# Microcontroller_schematic.net
KiCad netlist of a schematic drawn in Altium Designer
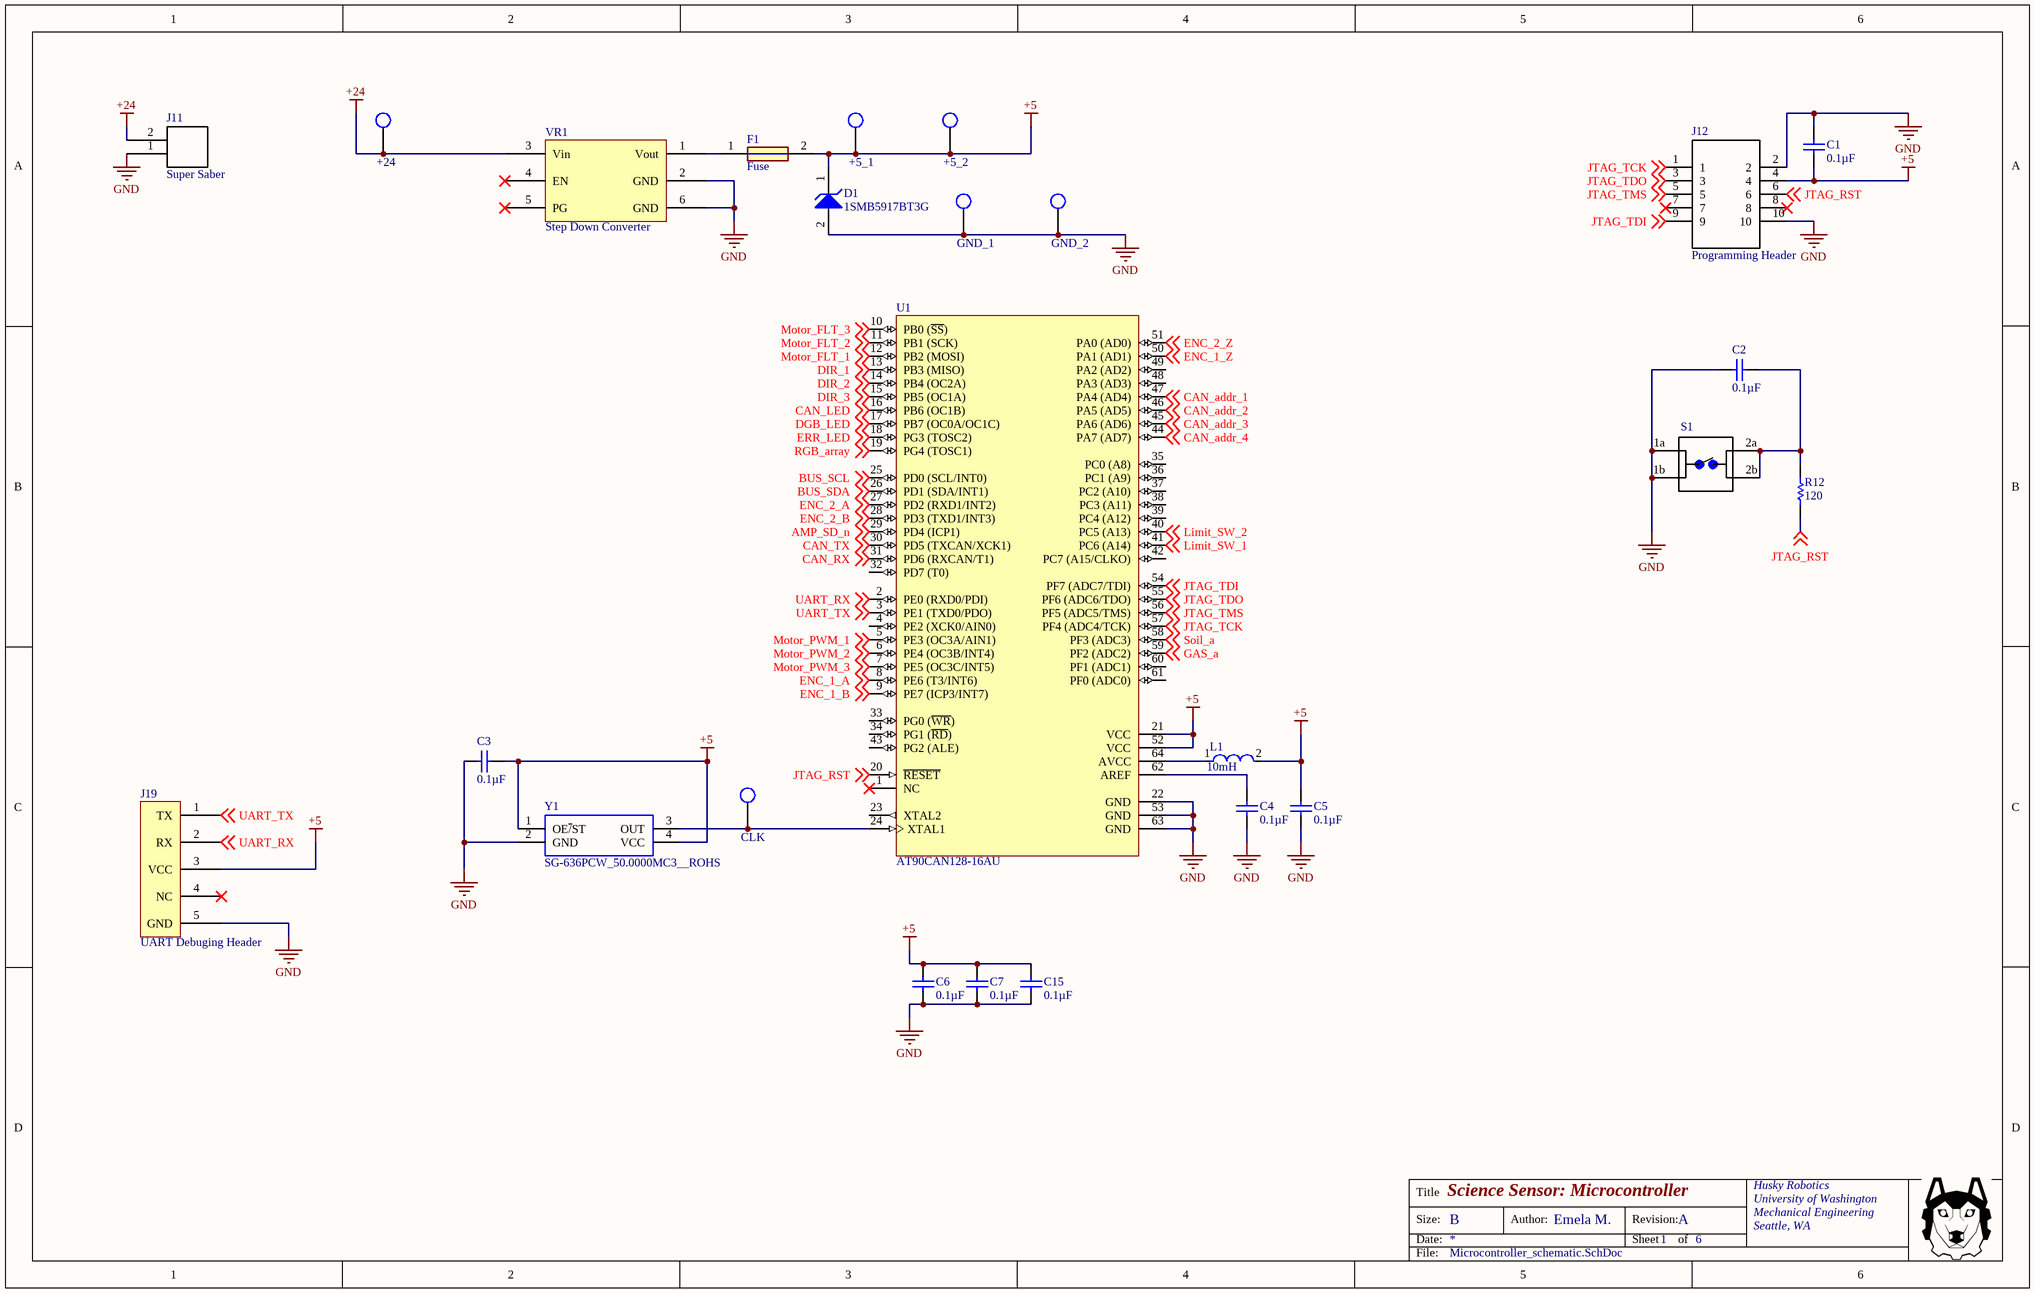
[diagram p0: Microcontroller_schematic.SchDoc]

(export (version "E")
  (design (tool "Eeschema 10.0.6"))
  (components
    (comp (ref "+5_1")
      (value "Test Point")
      (footprint "Test Point Through-hole")
      (libsource (lib "Husky Robotics Standard Library 2019-2020") (part "Test Point"))
    )
    (comp (ref "+5_2")
      (value "Test Point")
      (footprint "Test Point Through-hole")
      (libsource (lib "Husky Robotics Standard Library 2019-2020") (part "Test Point"))
    )
    (comp (ref "+24")
      (value "Test Point")
      (footprint "Test Point Through-hole")
      (libsource (lib "Husky Robotics Standard Library 2019-2020") (part "Test Point"))
    )
    (comp (ref "C1")
      (value "Capacitor 0805")
      (footprint "Cap 0805")
      (description "Standard Capacitor")
      (fields (field (name "MANUFACTURER") "AVX") (field (name "CAPACITANCE") "0.1µF"))
      (libsource (lib "Standard Cap") (part "Capacitor 0805"))
    )
    (comp (ref "C2")
      (value "Capacitor 0805")
      (footprint "Cap 0805")
      (description "Standard Capacitor")
      (fields (field (name "MANUFACTURER") "AVX") (field (name "CAPACITANCE") "0.1µF"))
      (libsource (lib "Standard Cap") (part "Capacitor 0805"))
    )
    (comp (ref "C3")
      (value "Capacitor 0805")
      (footprint "Cap 0805")
      (description "Standard Capacitor")
      (fields (field (name "MANUFACTURER") "AVX") (field (name "CAPACITANCE") "0.1µF"))
      (libsource (lib "Standard Cap") (part "Capacitor 0805"))
    )
    (comp (ref "C4")
      (value "Capacitor 0805")
      (footprint "Cap 0805")
      (description "Standard Capacitor")
      (fields (field (name "MANUFACTURER") "AVX") (field (name "CAPACITANCE") "0.1µF"))
      (libsource (lib "Standard Cap") (part "Capacitor 0805"))
    )
    (comp (ref "C5")
      (value "Capacitor 0805")
      (footprint "Cap 0805")
      (description "Standard Capacitor")
      (fields (field (name "MANUFACTURER") "AVX") (field (name "CAPACITANCE") "0.1µF"))
      (libsource (lib "Standard Cap") (part "Capacitor 0805"))
    )
    (comp (ref "C6")
      (value "Capacitor 0805")
      (footprint "Cap 0805")
      (description "Standard Capacitor")
      (fields (field (name "MANUFACTURER") "AVX") (field (name "CAPACITANCE") "0.1µF"))
      (libsource (lib "Standard Cap") (part "Capacitor 0805"))
    )
    (comp (ref "C7")
      (value "Capacitor 0805")
      (footprint "Cap 0805")
      (description "Standard Capacitor")
      (fields (field (name "MANUFACTURER") "AVX") (field (name "CAPACITANCE") "0.1µF"))
      (libsource (lib "Standard Cap") (part "Capacitor 0805"))
    )
    (comp (ref "C15")
      (value "Capacitor 0805")
      (footprint "Cap 0805")
      (description "Standard Capacitor")
      (fields (field (name "MANUFACTURER") "AVX") (field (name "CAPACITANCE") "0.1µF"))
      (libsource (lib "Standard Cap") (part "Capacitor 0805"))
    )
    (comp (ref "CLK")
      (value "Test Point")
      (footprint "Test Point Through-hole")
      (libsource (lib "Husky Robotics Standard Library 2019-2020") (part "Test Point"))
    )
    (comp (ref "D1")
      (value "1SMB5917BT3G")
      (footprint "ONSC-SMB-2-403A-03_H_V")
      (description "3 W Zener Voltage Regulator, 2-Pin SMB, Pb-Free, Tape and Reel")
      (fields (field (name "MANUFACTURER") "On Semiconductor"))
      (libsource (lib "Husky Robotics Standard Library 2019-2020") (part "Zener Diode 5.1V"))
    )
    (comp (ref "F1")
      (value "Fuse")
      (footprint "Fuse_Through_Hole - duplicate")
      (libsource (lib "Husky Robotics Standard Library 2019-2020") (part "Fuse"))
    )
    (comp (ref "GND_1")
      (value "Test Point")
      (footprint "Test Point Through-hole")
      (libsource (lib "Husky Robotics Standard Library 2019-2020") (part "Test Point"))
    )
    (comp (ref "GND_2")
      (value "Test Point")
      (footprint "Test Point Through-hole")
      (libsource (lib "Husky Robotics Standard Library 2019-2020") (part "Test Point"))
    )
    (comp (ref "J11")
      (value "Super Saber")
      (footprint "SuperSaber R/A")
      (libsource (lib "Husky Robotics Standard Library 2019-2020") (part "Super Saber"))
    )
    (comp (ref "J12")
      (value "Programming Header")
      (footprint "programming3D")
      (libsource (lib "Husky Robotics Standard Library 2019-2020") (part "Programming Header"))
    )
    (comp (ref "J19")
      (value "UART Debuging Header")
      (footprint "UART Debugging Header")
      (libsource (lib "Husky Robotics Standard Library 2019-2020") (part "UART Debuging Header"))
    )
    (comp (ref "L1")
      (value "10mH")
      (footprint "FP-CV201210-R10K-MFG")
      (description "FIXED IND 100NH 250MA 300 MOHM")
      (fields
        (field (name "TOLERANCE") "10%")
        (field (name "OCTOPART") "https://octopart.com/cv201210-r10k-bourns-2076708")
      )
      (libsource (lib "Altium Content Vault") (part "725321dda6339637d4d059423bc1c3c"))
    )
    (comp (ref "R12")
      (value "120")
      (footprint "RESC0805(2012)_N")
      (description "Generic 0805 Resistor")
      (fields (field (name "TOLERANCE") "5 %") (field (name "POWER") "0.125 W"))
      (libsource (lib "Husky Robotics Standard Library 2019-2020") (part "Resistor 0805"))
    )
    (comp (ref "S1")
      (value "1825910-7")
      (footprint "Switch 6mm 24V (NO)")
      (description "FSM4JAH=6MM TACT SWITCH, HIGH TEMP")
      (fields (field (name "MF") "TE Connectivity") (field (name "DIGI-KEY_PART_NUMBER") "450-1804-ND"))
      (libsource (lib "Husky Robotics Standard Library 2019-2020") (part "Switch 6mm 24V (NO)"))
    )
    (comp (ref "U1")
      (value "AT90CAN128-16AU")
      (footprint "64A_M")
      (libsource (lib "Altium Content Vault") (part "MC-8B-AT90CAN32-SQ64"))
    )
    (comp (ref "VR1")
      (value "Step Down Converter")
      (footprint "24V-5V Converter")
      (libsource (lib "Husky Robotics Standard Library 2019-2020") (part "24V-5V Pololu 2858"))
    )
    (comp (ref "Y1")
      (value "SG-636PCW_50.0000MC3__ROHS")
      (footprint "SG-636_3D")
      (description "Standard Clock Oscillators")
      (fields (field (name "MANUFACTURER_PART_NUMBER") "SG-636PCW 50.0000MC3: ROHS"))
      (libsource (lib "Husky Robotics Standard Library 2019-2020") (part "Oscilator"))
    )
  )
  (nets
    (net (code "1") (name "+5") (class "Default")
      (node (ref "+5_1") (pin "1") (pinfunction "1_1") (pintype "passive"))
      (node (ref "+5_2") (pin "1") (pinfunction "1_1") (pintype "passive"))
      (node (ref "C1") (pin "1") (pinfunction "1_1") (pintype "passive"))
      (node (ref "C15") (pin "2") (pinfunction "2_2") (pintype "passive"))
      (node (ref "C3") (pin "2") (pinfunction "2_2") (pintype "passive"))
      (node (ref "C5") (pin "2") (pinfunction "2_2") (pintype "passive"))
      (node (ref "C6") (pin "2") (pinfunction "2_2") (pintype "passive"))
      (node (ref "C7") (pin "2") (pinfunction "2_2") (pintype "passive"))
      (node (ref "D1") (pin "1") (pinfunction "K_1") (pintype "passive"))
      (node (ref "F1") (pin "2") (pinfunction "2_2") (pintype "passive"))
      (node (ref "J12") (pin "4") (pinfunction "4_4") (pintype "passive"))
      (node (ref "J19") (pin "3") (pinfunction "VCC_3") (pintype "passive"))
      (node (ref "L1") (pin "2") (pinfunction "2_2") (pintype "passive"))
      (node (ref "U1") (pin "21") (pinfunction "VCC_21") (pintype "power_in"))
      (node (ref "U1") (pin "52") (pinfunction "VCC_52") (pintype "power_in"))
      (node (ref "Y1") (pin "1") (pinfunction "OE~{/}ST_1") (pintype "passive"))
      (node (ref "Y1") (pin "4") (pinfunction "VCC_4") (pintype "power_in"))
    )
    (net (code "2") (name "+24") (class "Default")
      (node (ref "+24") (pin "1") (pinfunction "1_1") (pintype "passive"))
      (node (ref "J11") (pin "2") (pintype "passive"))
      (node (ref "VR1") (pin "3") (pinfunction "Vin_3") (pintype "passive"))
    )
    (net (code "3") (name "AMP_SD_n") (class "Default")
      (node (ref "U1") (pin "29") (pinfunction "PD4_(ICP1)_29") (pintype "bidirectional"))
    )
    (net (code "4") (name "BUS_SCL") (class "Default")
      (node (ref "U1") (pin "25") (pinfunction "PD0_(SCL/INT0)_25") (pintype "bidirectional"))
    )
    (net (code "5") (name "BUS_SDA") (class "Default")
      (node (ref "U1") (pin "26") (pinfunction "PD1_(SDA/INT1)_26") (pintype "bidirectional"))
    )
    (net (code "6") (name "CAN_LED") (class "Default")
      (node (ref "U1") (pin "16") (pinfunction "PB6_(OC1B)_16") (pintype "bidirectional"))
    )
    (net (code "7") (name "CAN_RX") (class "Default")
      (node (ref "U1") (pin "31") (pinfunction "PD6_(RXCAN/T1)_31") (pintype "bidirectional"))
    )
    (net (code "8") (name "CAN_TX") (class "Default")
      (node (ref "U1") (pin "30") (pinfunction "PD5_(TXCAN/XCK1)_30") (pintype "bidirectional"))
    )
    (net (code "9") (name "CAN_addr_1") (class "Default")
      (node (ref "U1") (pin "47") (pinfunction "PA4_(AD4)_47") (pintype "bidirectional"))
    )
    (net (code "10") (name "CAN_addr_2") (class "Default")
      (node (ref "U1") (pin "46") (pinfunction "PA5_(AD5)_46") (pintype "bidirectional"))
    )
    (net (code "11") (name "CAN_addr_3") (class "Default")
      (node (ref "U1") (pin "45") (pinfunction "PA6_(AD6)_45") (pintype "bidirectional"))
    )
    (net (code "12") (name "CAN_addr_4") (class "Default")
      (node (ref "U1") (pin "44") (pinfunction "PA7_(AD7)_44") (pintype "bidirectional"))
    )
    (net (code "13") (name "DGB_LED") (class "Default")
      (node (ref "U1") (pin "17") (pinfunction "PB7_(OC0A/OC1C)_17") (pintype "bidirectional"))
    )
    (net (code "14") (name "DIR_1") (class "Default")
      (node (ref "U1") (pin "13") (pinfunction "PB3_(MISO)_13") (pintype "bidirectional"))
    )
    (net (code "15") (name "DIR_2") (class "Default")
      (node (ref "U1") (pin "14") (pinfunction "PB4_(OC2A)_14") (pintype "bidirectional"))
    )
    (net (code "16") (name "DIR_3") (class "Default")
      (node (ref "U1") (pin "15") (pinfunction "PB5_(OC1A)_15") (pintype "bidirectional"))
    )
    (net (code "17") (name "ENC_1_A") (class "Default")
      (node (ref "U1") (pin "8") (pinfunction "PE6_(T3/INT6)_8") (pintype "bidirectional"))
    )
    (net (code "18") (name "ENC_1_B") (class "Default")
      (node (ref "U1") (pin "9") (pinfunction "PE7_(ICP3/INT7)_9") (pintype "bidirectional"))
    )
    (net (code "19") (name "ENC_1_Z") (class "Default")
      (node (ref "U1") (pin "50") (pinfunction "PA1_(AD1)_50") (pintype "bidirectional"))
    )
    (net (code "20") (name "ENC_2_A") (class "Default")
      (node (ref "U1") (pin "27") (pinfunction "PD2_(RXD1/INT2)_27") (pintype "bidirectional"))
    )
    (net (code "21") (name "ENC_2_B") (class "Default")
      (node (ref "U1") (pin "28") (pinfunction "PD3_(TXD1/INT3)_28") (pintype "bidirectional"))
    )
    (net (code "22") (name "ENC_2_Z") (class "Default")
      (node (ref "U1") (pin "51") (pinfunction "PA0_(AD0)_51") (pintype "bidirectional"))
    )
    (net (code "23") (name "ERR_LED") (class "Default")
      (node (ref "U1") (pin "18") (pinfunction "PG3_(TOSC2)_18") (pintype "bidirectional"))
    )
    (net (code "24") (name "GAS_a") (class "Default")
      (node (ref "U1") (pin "59") (pinfunction "PF2_(ADC2)_59") (pintype "bidirectional"))
    )
    (net (code "25") (name "GND") (class "Default")
      (node (ref "C1") (pin "2") (pinfunction "2_2") (pintype "passive"))
      (node (ref "C15") (pin "1") (pinfunction "1_1") (pintype "passive"))
      (node (ref "C2") (pin "1") (pinfunction "1_1") (pintype "passive"))
      (node (ref "C3") (pin "1") (pinfunction "1_1") (pintype "passive"))
      (node (ref "C4") (pin "1") (pinfunction "1_1") (pintype "passive"))
      (node (ref "C5") (pin "1") (pinfunction "1_1") (pintype "passive"))
      (node (ref "C6") (pin "1") (pinfunction "1_1") (pintype "passive"))
      (node (ref "C7") (pin "1") (pinfunction "1_1") (pintype "passive"))
      (node (ref "D1") (pin "2") (pinfunction "A_2") (pintype "passive"))
      (node (ref "GND_1") (pin "1") (pinfunction "1_1") (pintype "passive"))
      (node (ref "GND_2") (pin "1") (pinfunction "1_1") (pintype "passive"))
      (node (ref "J11") (pin "1") (pintype "passive"))
      (node (ref "J12") (pin "10") (pinfunction "10_10") (pintype "passive"))
      (node (ref "J12") (pin "2") (pinfunction "2_2") (pintype "passive"))
      (node (ref "J19") (pin "5") (pinfunction "GND_5") (pintype "passive"))
      (node (ref "S1") (pin "1a") (pinfunction "1a_1a") (pintype "passive"))
      (node (ref "S1") (pin "1b") (pinfunction "1b_1b") (pintype "passive"))
      (node (ref "U1") (pin "22") (pinfunction "GND_22") (pintype "power_in"))
      (node (ref "U1") (pin "53") (pinfunction "GND_53") (pintype "power_in"))
      (node (ref "U1") (pin "63") (pinfunction "GND_63") (pintype "power_in"))
      (node (ref "VR1") (pin "2") (pinfunction "GND_2") (pintype "passive"))
      (node (ref "VR1") (pin "6") (pinfunction "GND_6") (pintype "passive"))
      (node (ref "Y1") (pin "2") (pinfunction "GND_2") (pintype "passive"))
    )
    (net (code "26") (name "JTAG_RST") (class "Default")
      (node (ref "J12") (pin "6") (pinfunction "6_6") (pintype "passive"))
      (node (ref "R12") (pin "1") (pinfunction "1_1") (pintype "passive"))
      (node (ref "U1") (pin "20") (pinfunction "~{RESET}_20") (pintype "input"))
    )
    (net (code "27") (name "JTAG_TCK") (class "Default")
      (node (ref "J12") (pin "1") (pinfunction "1_1") (pintype "passive"))
      (node (ref "U1") (pin "57") (pinfunction "PF4_(ADC4/TCK)_57") (pintype "bidirectional"))
    )
    (net (code "28") (name "JTAG_TDI") (class "Default")
      (node (ref "J12") (pin "9") (pinfunction "9_9") (pintype "passive"))
      (node (ref "U1") (pin "54") (pinfunction "PF7_(ADC7/TDI)_54") (pintype "bidirectional"))
    )
    (net (code "29") (name "JTAG_TDO") (class "Default")
      (node (ref "J12") (pin "3") (pinfunction "3_3") (pintype "passive"))
      (node (ref "U1") (pin "55") (pinfunction "PF6_(ADC6/TDO)_55") (pintype "bidirectional"))
    )
    (net (code "30") (name "JTAG_TMS") (class "Default")
      (node (ref "J12") (pin "5") (pinfunction "5_5") (pintype "passive"))
      (node (ref "U1") (pin "56") (pinfunction "PF5_(ADC5/TMS)_56") (pintype "bidirectional"))
    )
    (net (code "31") (name "Limit_SW_1") (class "Default")
      (node (ref "U1") (pin "41") (pinfunction "PC6_(A14)_41") (pintype "bidirectional"))
    )
    (net (code "32") (name "Limit_SW_2") (class "Default")
      (node (ref "U1") (pin "40") (pinfunction "PC5_(A13)_40") (pintype "bidirectional"))
    )
    (net (code "33") (name "Motor_FLT_1") (class "Default")
      (node (ref "U1") (pin "12") (pinfunction "PB2_(MOSI)_12") (pintype "bidirectional"))
    )
    (net (code "34") (name "Motor_FLT_2") (class "Default")
      (node (ref "U1") (pin "11") (pinfunction "PB1_(SCK)_11") (pintype "bidirectional"))
    )
    (net (code "35") (name "Motor_FLT_3") (class "Default")
      (node (ref "U1") (pin "10") (pinfunction "PB0_(~{SS})_10") (pintype "bidirectional"))
    )
    (net (code "36") (name "Motor_PWM_1") (class "Default")
      (node (ref "U1") (pin "5") (pinfunction "PE3_(OC3A/AIN1)_5") (pintype "bidirectional"))
    )
    (net (code "37") (name "Motor_PWM_2") (class "Default")
      (node (ref "U1") (pin "6") (pinfunction "PE4_(OC3B/INT4)_6") (pintype "bidirectional"))
    )
    (net (code "38") (name "Motor_PWM_3") (class "Default")
      (node (ref "U1") (pin "7") (pinfunction "PE5_(OC3C/INT5)_7") (pintype "bidirectional"))
    )
    (net (code "39") (name "Net-(C2-Pad2)") (class "Default")
      (node (ref "C2") (pin "2") (pinfunction "2_2") (pintype "passive"))
      (node (ref "R12") (pin "2") (pinfunction "2_2") (pintype "passive"))
      (node (ref "S1") (pin "2a") (pinfunction "2a_2a") (pintype "passive"))
      (node (ref "S1") (pin "2b") (pinfunction "2b_2b") (pintype "passive"))
    )
    (net (code "40") (name "Net-(U1-AREF)") (class "Default")
      (node (ref "C4") (pin "2") (pinfunction "2_2") (pintype "passive"))
      (node (ref "U1") (pin "62") (pinfunction "AREF_62") (pintype "power_in"))
    )
    (net (code "41") (name "Net-(U1-AVCC)") (class "Default")
      (node (ref "L1") (pin "1") (pinfunction "1_1") (pintype "passive"))
      (node (ref "U1") (pin "64") (pinfunction "AVCC_64") (pintype "power_in"))
    )
    (net (code "42") (name "Net-(U1-XTAL1)") (class "Default")
      (node (ref "CLK") (pin "1") (pinfunction "1_1") (pintype "passive"))
      (node (ref "U1") (pin "24") (pinfunction "XTAL1_24") (pintype "input"))
      (node (ref "Y1") (pin "3") (pinfunction "OUT_3") (pintype "passive"))
    )
    (net (code "43") (name "Net-(VR1-Vout)") (class "Default")
      (node (ref "F1") (pin "1") (pinfunction "1_1") (pintype "passive"))
      (node (ref "VR1") (pin "1") (pinfunction "Vout_1") (pintype "passive"))
    )
    (net (code "44") (name "RGB_array") (class "Default")
      (node (ref "U1") (pin "19") (pinfunction "PG4_(TOSC1)_19") (pintype "bidirectional"))
    )
    (net (code "45") (name "Soil_a") (class "Default")
      (node (ref "U1") (pin "58") (pinfunction "PF3_(ADC3)_58") (pintype "bidirectional"))
    )
    (net (code "46") (name "UART_RX") (class "Default")
      (node (ref "J19") (pin "2") (pinfunction "RX_2") (pintype "passive"))
      (node (ref "U1") (pin "2") (pinfunction "PE0_(RXD0/PDI)_2") (pintype "bidirectional"))
    )
    (net (code "47") (name "UART_TX") (class "Default")
      (node (ref "J19") (pin "1") (pinfunction "TX_1") (pintype "passive"))
      (node (ref "U1") (pin "3") (pinfunction "PE1_(TXD0/PDO)_3") (pintype "bidirectional"))
    )
    (net (code "48") (name "unconnected-(J12-Pad7)") (class "Default")
      (node (ref "J12") (pin "7") (pinfunction "7_7") (pintype "passive+no_connect"))
    )
    (net (code "49") (name "unconnected-(J12-Pad8)") (class "Default")
      (node (ref "J12") (pin "8") (pinfunction "8_8") (pintype "passive+no_connect"))
    )
    (net (code "50") (name "unconnected-(J19-NC-Pad4)") (class "Default")
      (node (ref "J19") (pin "4") (pinfunction "NC_4") (pintype "passive+no_connect"))
    )
    (net (code "51") (name "unconnected-(U1-NC-Pad1)") (class "Default")
      (node (ref "U1") (pin "1") (pinfunction "NC_1") (pintype "passive+no_connect"))
    )
    (net (code "52") (name "unconnected-(U1-PA2_(AD2)-Pad49)") (class "Default")
      (node (ref "U1") (pin "49") (pinfunction "PA2_(AD2)_49") (pintype "bidirectional"))
    )
    (net (code "53") (name "unconnected-(U1-PA3_(AD3)-Pad48)") (class "Default")
      (node (ref "U1") (pin "48") (pinfunction "PA3_(AD3)_48") (pintype "bidirectional"))
    )
    (net (code "54") (name "unconnected-(U1-PC0_(A8)-Pad35)") (class "Default")
      (node (ref "U1") (pin "35") (pinfunction "PC0_(A8)_35") (pintype "bidirectional"))
    )
    (net (code "55") (name "unconnected-(U1-PC1_(A9)-Pad36)") (class "Default")
      (node (ref "U1") (pin "36") (pinfunction "PC1_(A9)_36") (pintype "bidirectional"))
    )
    (net (code "56") (name "unconnected-(U1-PC2_(A10)-Pad37)") (class "Default")
      (node (ref "U1") (pin "37") (pinfunction "PC2_(A10)_37") (pintype "bidirectional"))
    )
    (net (code "57") (name "unconnected-(U1-PC3_(A11)-Pad38)") (class "Default")
      (node (ref "U1") (pin "38") (pinfunction "PC3_(A11)_38") (pintype "bidirectional"))
    )
    (net (code "58") (name "unconnected-(U1-PC4_(A12)-Pad39)") (class "Default")
      (node (ref "U1") (pin "39") (pinfunction "PC4_(A12)_39") (pintype "bidirectional"))
    )
    (net (code "59") (name "unconnected-(U1-PC7_(A15{slash}CLKO)-Pad42)") (class "Default")
      (node (ref "U1") (pin "42") (pinfunction "PC7_(A15/CLKO)_42") (pintype "bidirectional"))
    )
    (net (code "60") (name "unconnected-(U1-PD7_(T0)-Pad32)") (class "Default")
      (node (ref "U1") (pin "32") (pinfunction "PD7_(T0)_32") (pintype "bidirectional"))
    )
    (net (code "61") (name "unconnected-(U1-PE2_(XCK0{slash}AIN0)-Pad4)") (class "Default")
      (node (ref "U1") (pin "4") (pinfunction "PE2_(XCK0/AIN0)_4") (pintype "bidirectional"))
    )
    (net (code "62") (name "unconnected-(U1-PF0_(ADC0)-Pad61)") (class "Default")
      (node (ref "U1") (pin "61") (pinfunction "PF0_(ADC0)_61") (pintype "bidirectional"))
    )
    (net (code "63") (name "unconnected-(U1-PF1_(ADC1)-Pad60)") (class "Default")
      (node (ref "U1") (pin "60") (pinfunction "PF1_(ADC1)_60") (pintype "bidirectional"))
    )
    (net (code "64") (name "unconnected-(U1-PG0_(~{WR})-Pad33)") (class "Default")
      (node (ref "U1") (pin "33") (pinfunction "PG0_(~{WR})_33") (pintype "bidirectional"))
    )
    (net (code "65") (name "unconnected-(U1-PG1_(~{RD})-Pad34)") (class "Default")
      (node (ref "U1") (pin "34") (pinfunction "PG1_(~{RD})_34") (pintype "bidirectional"))
    )
    (net (code "66") (name "unconnected-(U1-PG2_(ALE)-Pad43)") (class "Default")
      (node (ref "U1") (pin "43") (pinfunction "PG2_(ALE)_43") (pintype "bidirectional"))
    )
    (net (code "67") (name "unconnected-(U1-XTAL2-Pad23)") (class "Default")
      (node (ref "U1") (pin "23") (pinfunction "XTAL2_23") (pintype "output"))
    )
    (net (code "68") (name "unconnected-(VR1-EN-Pad4)") (class "Default")
      (node (ref "VR1") (pin "4") (pinfunction "EN_4") (pintype "passive+no_connect"))
    )
    (net (code "69") (name "unconnected-(VR1-PG-Pad5)") (class "Default")
      (node (ref "VR1") (pin "5") (pinfunction "PG_5") (pintype "passive+no_connect"))
    )
  )
)
